# Mini_PLC_USB.net
KiCad netlist of a schematic drawn in EAGLE
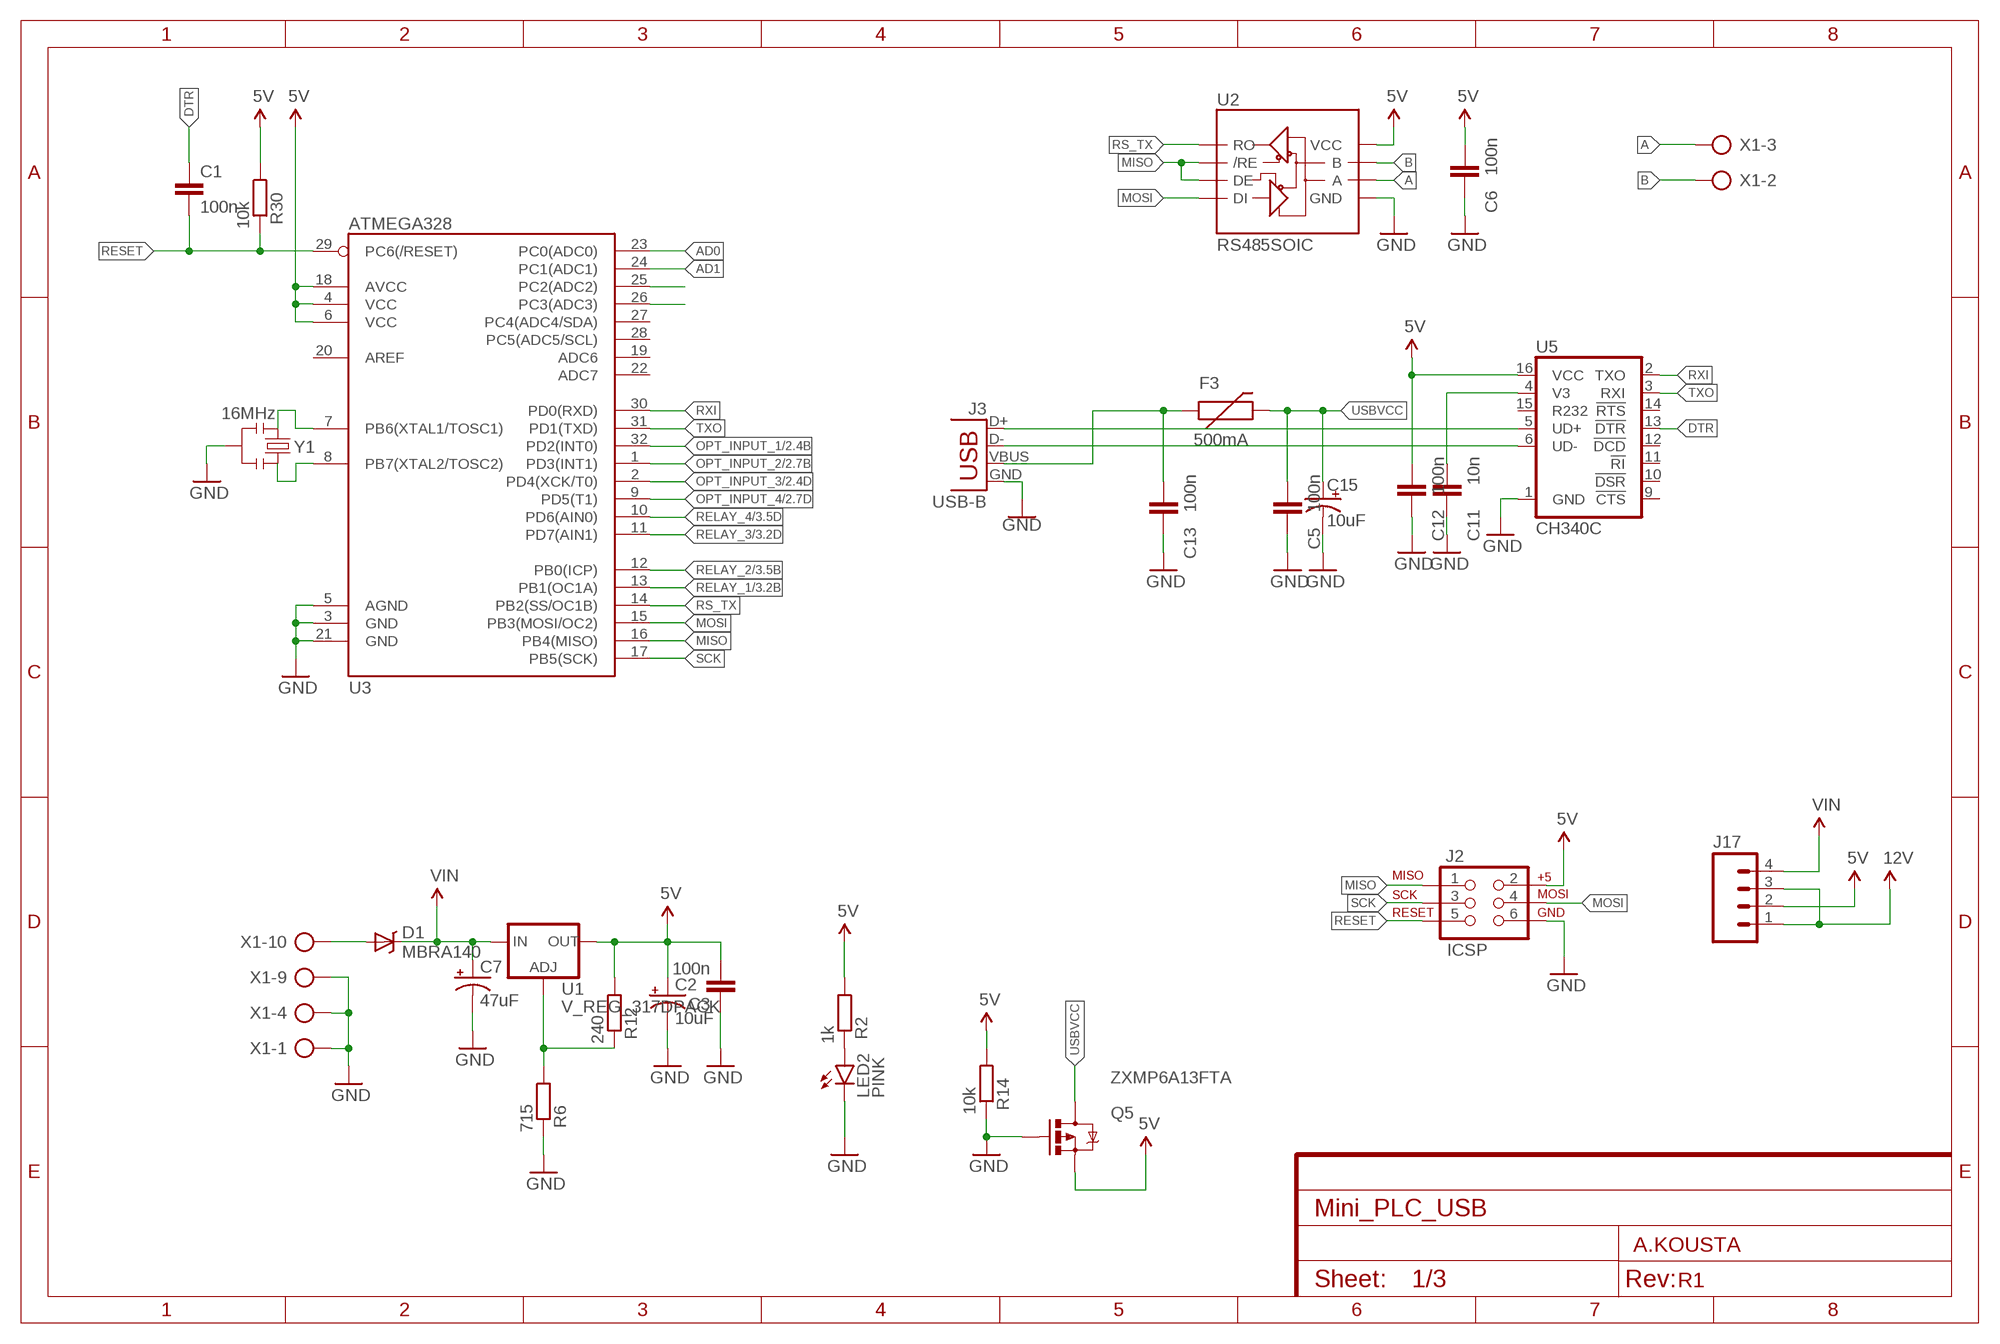
[diagram p0: schematic, sheet 1]
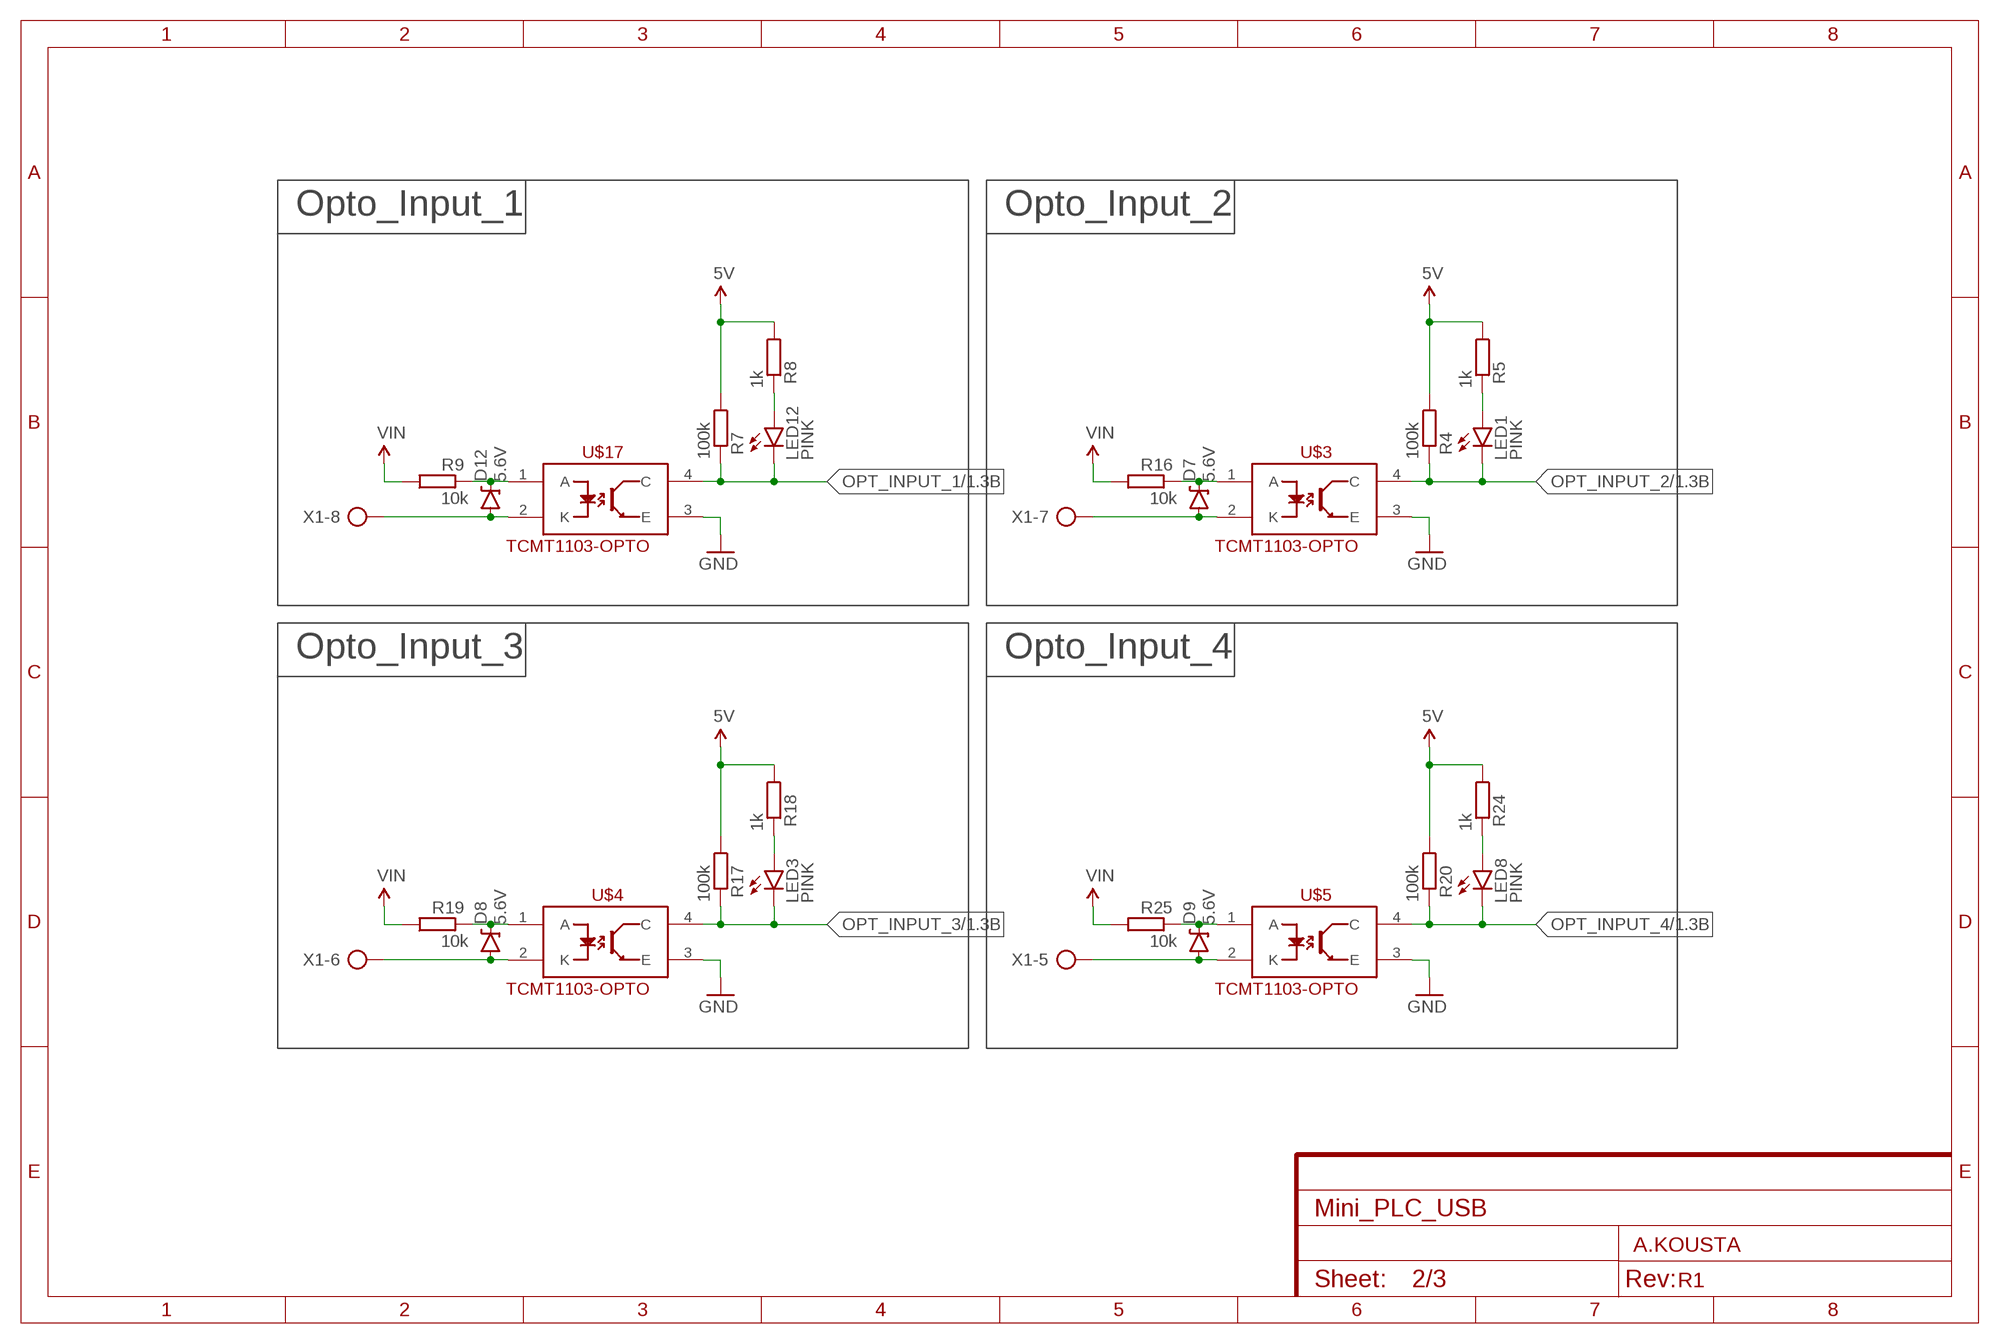
[diagram p1: schematic, sheet 2]
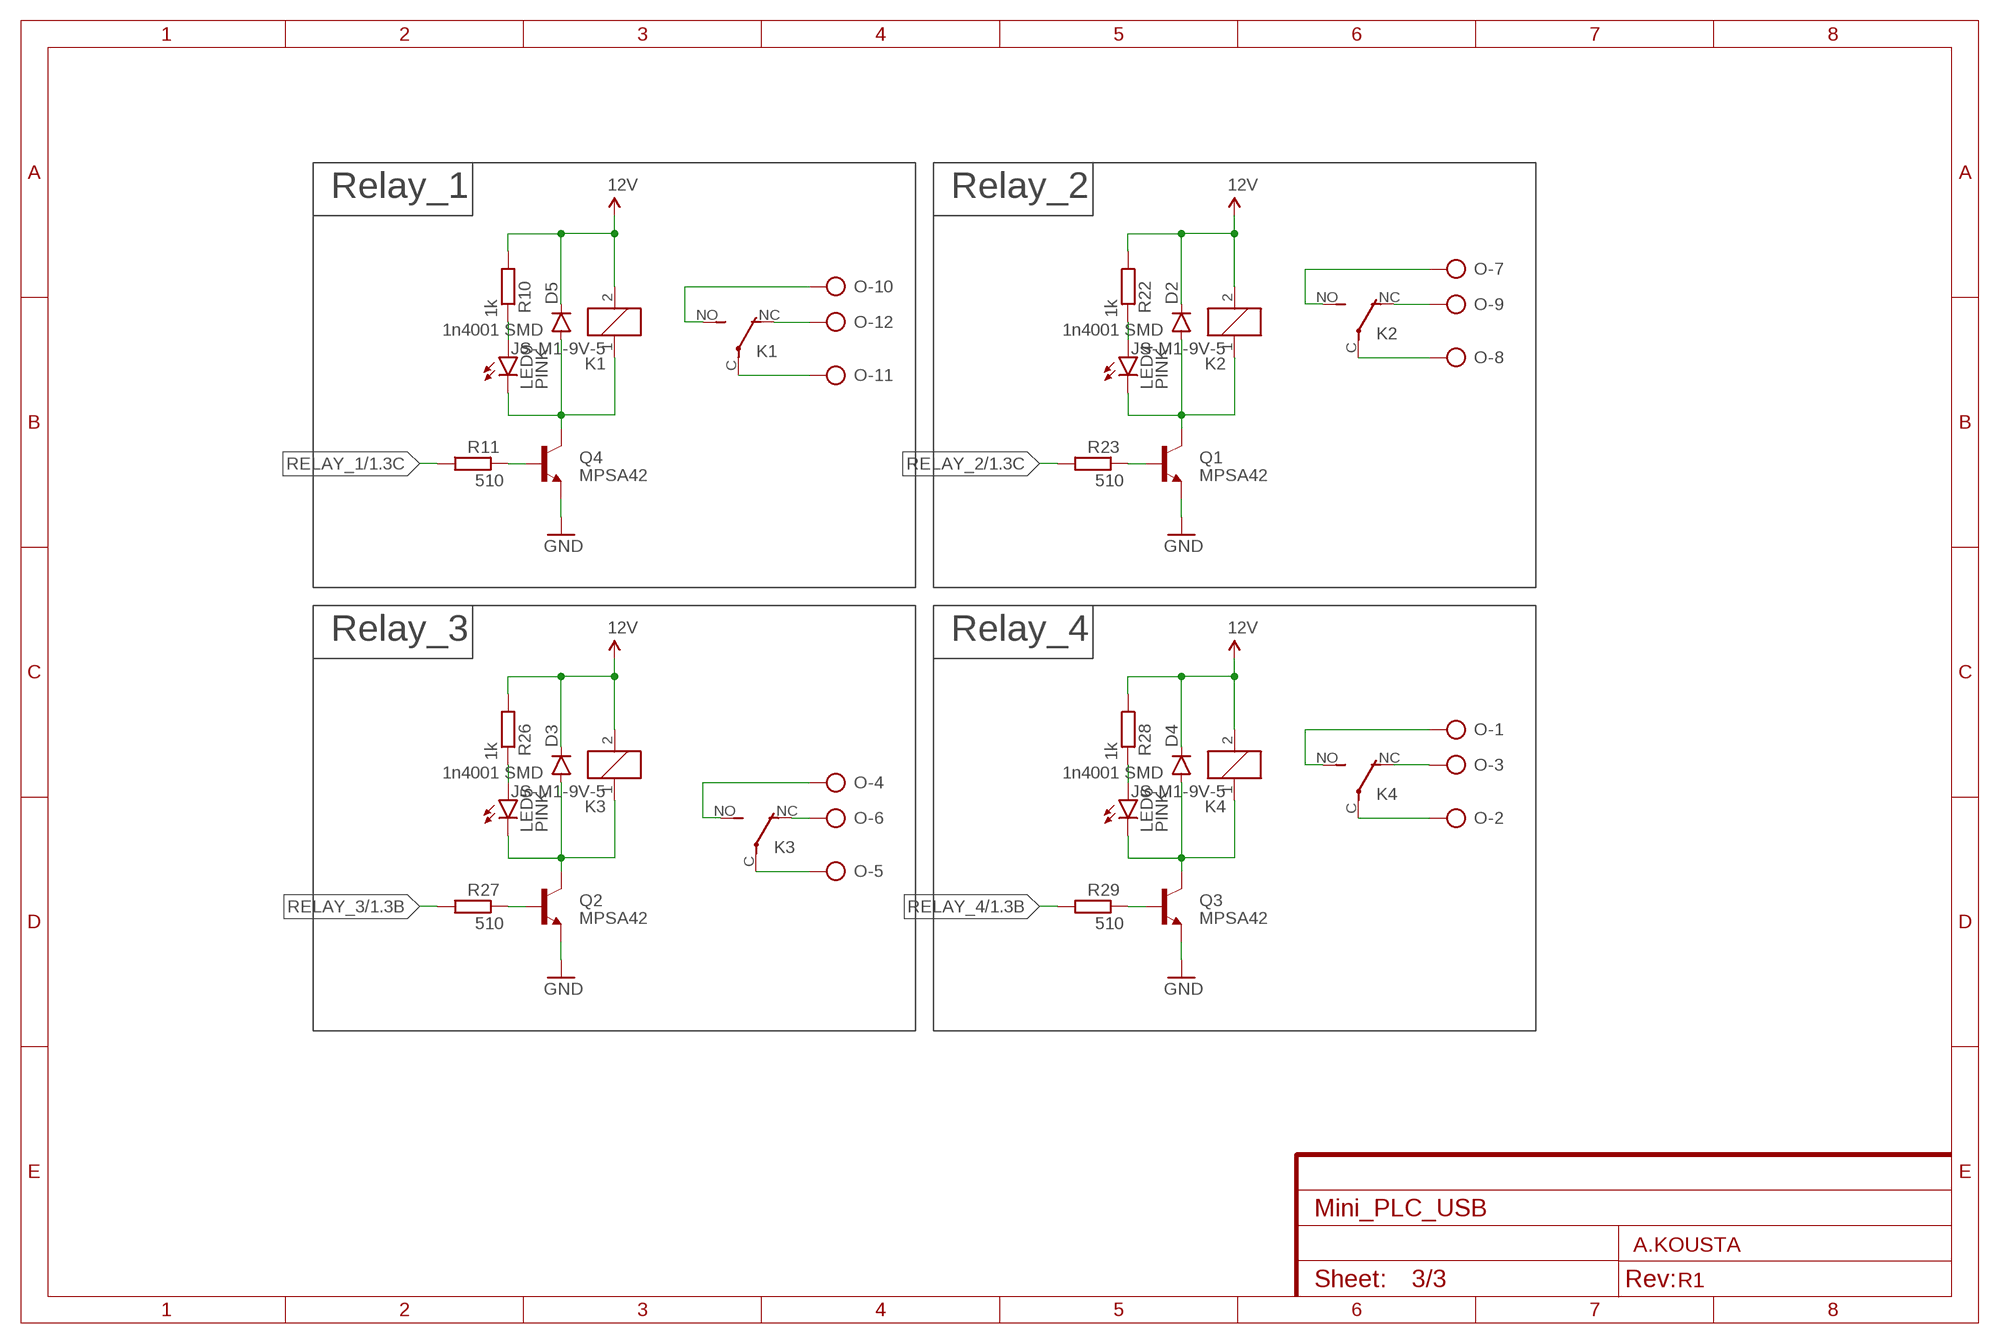
[diagram p2: schematic, sheet 3]

(export (version "E")
  (design (tool "Eeschema 10.0.6"))
  (components
    (comp (ref "D2")
      (value "1n4001 SMD")
      (footprint "eagle-import:SOD-123")
      (libsource (lib "eagle-import") (part "DIODESOD123"))
    )
    (comp (ref "D3")
      (value "1n4001 SMD")
      (footprint "eagle-import:SOD-123")
      (libsource (lib "eagle-import") (part "DIODESOD123"))
    )
    (comp (ref "D4")
      (value "1n4001 SMD")
      (footprint "eagle-import:SOD-123")
      (libsource (lib "eagle-import") (part "DIODESOD123"))
    )
    (comp (ref "D5")
      (value "1n4001 SMD")
      (footprint "eagle-import:SOD-123")
      (libsource (lib "eagle-import") (part "DIODESOD123"))
    )
    (comp (ref "K1")
      (value "JS-M1-9V-5")
      (footprint "eagle-import:JS-M")
      (libsource (lib "eagle-import") (part "JS-M1-9V-5"))
    )
    (comp (ref "K2")
      (value "JS-M1-9V-5")
      (footprint "eagle-import:JS-M")
      (libsource (lib "eagle-import") (part "JS-M1-9V-5"))
    )
    (comp (ref "K3")
      (value "JS-M1-9V-5")
      (footprint "eagle-import:JS-M")
      (libsource (lib "eagle-import") (part "JS-M1-9V-5"))
    )
    (comp (ref "K4")
      (value "JS-M1-9V-5")
      (footprint "eagle-import:JS-M")
      (libsource (lib "eagle-import") (part "JS-M1-9V-5"))
    )
    (comp (ref "LED4")
      (value "PINK")
      (footprint "eagle-import:LED-1206@1")
      (libsource (lib "eagle-import") (part "LED-PINK1206"))
    )
    (comp (ref "LED5")
      (value "PINK")
      (footprint "eagle-import:LED-1206@1")
      (libsource (lib "eagle-import") (part "LED-PINK1206"))
    )
    (comp (ref "LED6")
      (value "PINK")
      (footprint "eagle-import:LED-1206@1")
      (libsource (lib "eagle-import") (part "LED-PINK1206"))
    )
    (comp (ref "LED9")
      (value "PINK")
      (footprint "eagle-import:LED-1206@1")
      (libsource (lib "eagle-import") (part "LED-PINK1206"))
    )
    (comp (ref "O")
      (value "AK500/12-H")
      (footprint "eagle-import:AK500_12-H")
      (libsource (lib "eagle-import") (part "AK500/12-H"))
    )
    (comp (ref "Q1")
      (value "MPSA42")
      (footprint "eagle-import:SOT23-3@1")
      (libsource (lib "eagle-import") (part "TRANSISTOR_NPNMPSA42"))
    )
    (comp (ref "Q2")
      (value "MPSA42")
      (footprint "eagle-import:SOT23-3@1")
      (libsource (lib "eagle-import") (part "TRANSISTOR_NPNMPSA42"))
    )
    (comp (ref "Q3")
      (value "MPSA42")
      (footprint "eagle-import:SOT23-3@1")
      (libsource (lib "eagle-import") (part "TRANSISTOR_NPNMPSA42"))
    )
    (comp (ref "Q4")
      (value "MPSA42")
      (footprint "eagle-import:SOT23-3@1")
      (libsource (lib "eagle-import") (part "TRANSISTOR_NPNMPSA42"))
    )
    (comp (ref "R10")
      (value "1k")
      (footprint "eagle-import:M1206")
      (libsource (lib "eagle-import") (part "R-EU_M1206"))
    )
    (comp (ref "R11")
      (value "510")
      (footprint "eagle-import:M1206")
      (libsource (lib "eagle-import") (part "R-EU_M1206"))
    )
    (comp (ref "R22")
      (value "1k")
      (footprint "eagle-import:M1206")
      (libsource (lib "eagle-import") (part "R-EU_M1206"))
    )
    (comp (ref "R23")
      (value "510")
      (footprint "eagle-import:M1206")
      (libsource (lib "eagle-import") (part "R-EU_M1206"))
    )
    (comp (ref "R26")
      (value "1k")
      (footprint "eagle-import:M1206")
      (libsource (lib "eagle-import") (part "R-EU_M1206"))
    )
    (comp (ref "R27")
      (value "510")
      (footprint "eagle-import:M1206")
      (libsource (lib "eagle-import") (part "R-EU_M1206"))
    )
    (comp (ref "R28")
      (value "1k")
      (footprint "eagle-import:M1206")
      (libsource (lib "eagle-import") (part "R-EU_M1206"))
    )
    (comp (ref "R29")
      (value "510")
      (footprint "eagle-import:M1206")
      (libsource (lib "eagle-import") (part "R-EU_M1206"))
    )
    (comp (ref "D7")
      (value "5.6V")
      (footprint "eagle-import:SOD-323")
      (libsource (lib "eagle-import") (part "DIODE-ZENER5.6V"))
    )
    (comp (ref "D8")
      (value "5.6V")
      (footprint "eagle-import:SOD-323")
      (libsource (lib "eagle-import") (part "DIODE-ZENER5.6V"))
    )
    (comp (ref "D9")
      (value "5.6V")
      (footprint "eagle-import:SOD-323")
      (libsource (lib "eagle-import") (part "DIODE-ZENER5.6V"))
    )
    (comp (ref "D12")
      (value "5.6V")
      (footprint "eagle-import:SOD-323")
      (libsource (lib "eagle-import") (part "DIODE-ZENER5.6V"))
    )
    (comp (ref "LED1")
      (value "PINK")
      (footprint "eagle-import:LED-1206@1")
      (libsource (lib "eagle-import") (part "LED-PINK1206"))
    )
    (comp (ref "LED3")
      (value "PINK")
      (footprint "eagle-import:LED-1206@1")
      (libsource (lib "eagle-import") (part "LED-PINK1206"))
    )
    (comp (ref "LED8")
      (value "PINK")
      (footprint "eagle-import:LED-1206@1")
      (libsource (lib "eagle-import") (part "LED-PINK1206"))
    )
    (comp (ref "LED12")
      (value "PINK")
      (footprint "eagle-import:LED-1206@1")
      (libsource (lib "eagle-import") (part "LED-PINK1206"))
    )
    (comp (ref "R4")
      (value "100k")
      (footprint "eagle-import:M1206")
      (libsource (lib "eagle-import") (part "R-EU_M1206"))
    )
    (comp (ref "R5")
      (value "1k")
      (footprint "eagle-import:M1206")
      (libsource (lib "eagle-import") (part "R-EU_M1206"))
    )
    (comp (ref "R7")
      (value "100k")
      (footprint "eagle-import:M1206")
      (libsource (lib "eagle-import") (part "R-EU_M1206"))
    )
    (comp (ref "R8")
      (value "1k")
      (footprint "eagle-import:M1206")
      (libsource (lib "eagle-import") (part "R-EU_M1206"))
    )
    (comp (ref "R9")
      (value "10k")
      (footprint "eagle-import:M1206")
      (libsource (lib "eagle-import") (part "R-EU_M1206"))
    )
    (comp (ref "R16")
      (value "10k")
      (footprint "eagle-import:M1206")
      (libsource (lib "eagle-import") (part "R-EU_M1206"))
    )
    (comp (ref "R17")
      (value "100k")
      (footprint "eagle-import:M1206")
      (libsource (lib "eagle-import") (part "R-EU_M1206"))
    )
    (comp (ref "R18")
      (value "1k")
      (footprint "eagle-import:M1206")
      (libsource (lib "eagle-import") (part "R-EU_M1206"))
    )
    (comp (ref "R19")
      (value "10k")
      (footprint "eagle-import:M1206")
      (libsource (lib "eagle-import") (part "R-EU_M1206"))
    )
    (comp (ref "R20")
      (value "100k")
      (footprint "eagle-import:M1206")
      (libsource (lib "eagle-import") (part "R-EU_M1206"))
    )
    (comp (ref "R24")
      (value "1k")
      (footprint "eagle-import:M1206")
      (libsource (lib "eagle-import") (part "R-EU_M1206"))
    )
    (comp (ref "R25")
      (value "10k")
      (footprint "eagle-import:M1206")
      (libsource (lib "eagle-import") (part "R-EU_M1206"))
    )
    (comp (ref "U$3")
      (value "TCMT1103-OPTO")
      (footprint "eagle-import:SSOP-4")
      (libsource (lib "eagle-import") (part "TCMT1103-OPTO"))
    )
    (comp (ref "U$4")
      (value "TCMT1103-OPTO")
      (footprint "eagle-import:SSOP-4")
      (libsource (lib "eagle-import") (part "TCMT1103-OPTO"))
    )
    (comp (ref "U$5")
      (value "TCMT1103-OPTO")
      (footprint "eagle-import:SSOP-4")
      (libsource (lib "eagle-import") (part "TCMT1103-OPTO"))
    )
    (comp (ref "U$17")
      (value "TCMT1103-OPTO")
      (footprint "eagle-import:SSOP-4")
      (libsource (lib "eagle-import") (part "TCMT1103-OPTO"))
    )
    (comp (ref "X1")
      (value "AK500/10-H")
      (footprint "eagle-import:AK500_10-H")
      (libsource (lib "eagle-import") (part "AK500/10-H"))
    )
    (comp (ref "C1")
      (value "100n")
      (footprint "eagle-import:C1206")
      (libsource (lib "eagle-import") (part "C-EUC1206"))
    )
    (comp (ref "C2")
      (value "10uF")
      (footprint "eagle-import:EIA3216")
      (libsource (lib "eagle-import") (part "CAP_POL1206"))
    )
    (comp (ref "C3")
      (value "100n")
      (footprint "eagle-import:C1206")
      (libsource (lib "eagle-import") (part "C-EUC1206"))
    )
    (comp (ref "C5")
      (value "100n")
      (footprint "eagle-import:C1206")
      (libsource (lib "eagle-import") (part "C-EUC1206"))
    )
    (comp (ref "C6")
      (value "100n")
      (footprint "eagle-import:C1206")
      (libsource (lib "eagle-import") (part "C-EUC1206"))
    )
    (comp (ref "C7")
      (value "47uF")
      (footprint "eagle-import:PANASONIC_D")
      (fields (field (name "MF") "PANASONIC ELECTRONIC COMPONENTS") (field (name "MPN") "EEE1CA470SP"))
      (libsource (lib "eagle-import") (part "CAP_POLD"))
    )
    (comp (ref "C11")
      (value "10n")
      (footprint "eagle-import:C1206")
      (libsource (lib "eagle-import") (part "C-EUC1206"))
    )
    (comp (ref "C12")
      (value "100n")
      (footprint "eagle-import:C1206")
      (libsource (lib "eagle-import") (part "C-EUC1206"))
    )
    (comp (ref "C13")
      (value "100n")
      (footprint "eagle-import:C1206")
      (libsource (lib "eagle-import") (part "C-EUC1206"))
    )
    (comp (ref "C15")
      (value "10uF")
      (footprint "eagle-import:EIA3216")
      (libsource (lib "eagle-import") (part "10UF-POLAR-EIA3216-16V-10%(TANT)"))
    )
    (comp (ref "D1")
      (value "MBRA140")
      (footprint "eagle-import:SMA-DIODE")
      (fields (field (name "MF") "DIODES INC.") (field (name "MPN") "B140-13-F"))
      (libsource (lib "eagle-import") (part "DIODE-SCHOTTKY_"))
    )
    (comp (ref "F3")
      (value "500mA")
      (footprint "eagle-import:PTC-1206")
      (libsource (lib "eagle-import") (part "PTCSMD"))
    )
    (comp (ref "J2")
      (value "ICSP")
      (footprint "eagle-import:2X3")
      (libsource (lib "eagle-import") (part "AVR_SPI_PRG_6PTH"))
    )
    (comp (ref "J3")
      (value "USB-B")
      (footprint "eagle-import:USB-B-PTH")
      (fields (field (name "MPN") "USB-B-S-RA"))
      (libsource (lib "eagle-import") (part "USBPTH"))
    )
    (comp (ref "J17")
      (value "M04PTH")
      (footprint "eagle-import:1X04")
      (libsource (lib "eagle-import") (part "M04PTH"))
    )
    (comp (ref "LED2")
      (value "PINK")
      (footprint "eagle-import:LED-1206@1")
      (libsource (lib "eagle-import") (part "LED-PINK1206"))
    )
    (comp (ref "Q5")
      (value "ZXMP6A13FTA")
      (footprint "eagle-import:SOT23-3")
      (libsource (lib "eagle-import") (part "MOSFET-PCHANNELSMD"))
    )
    (comp (ref "R2")
      (value "1k")
      (footprint "eagle-import:M1206")
      (libsource (lib "eagle-import") (part "R-EU_M1206"))
    )
    (comp (ref "R6")
      (value "715")
      (footprint "eagle-import:M1206")
      (libsource (lib "eagle-import") (part "R-EU_M1206"))
    )
    (comp (ref "R12")
      (value "240")
      (footprint "eagle-import:M1206")
      (libsource (lib "eagle-import") (part "R-EU_M1206"))
    )
    (comp (ref "R14")
      (value "10k")
      (footprint "eagle-import:M1206")
      (libsource (lib "eagle-import") (part "R-EU_M1206"))
    )
    (comp (ref "R30")
      (value "10k")
      (footprint "eagle-import:M1206")
      (libsource (lib "eagle-import") (part "R-EU_M1206"))
    )
    (comp (ref "U1")
      (value "V_REG_317DPACK")
      (footprint "eagle-import:V-REG_DPACK")
      (libsource (lib "eagle-import") (part "V_REG_317DPACK"))
    )
    (comp (ref "U2")
      (value "RS485SOIC")
      (footprint "eagle-import:SO08")
      (libsource (lib "eagle-import") (part "RS485SOIC"))
    )
    (comp (ref "U3")
      (value "ATMEGA328")
      (footprint "eagle-import:TQFP32-08")
      (libsource (lib "eagle-import") (part "ATMEGA168"))
    )
    (comp (ref "U5")
      (value "CH340C")
      (footprint "eagle-import:SO016")
      (libsource (lib "eagle-import") (part "CH340C"))
    )
    (comp (ref "Y1")
      (value "16MHz")
      (footprint "eagle-import:RESONATOR-SMD")
      (libsource (lib "eagle-import") (part "RESONATORSMD"))
    )
  )
  (nets
    (net (code "1") (name "5V") (class "Default")
      (node (ref "C12") (pin "2") (pinfunction "2_2") (pintype "passive"))
      (node (ref "C2") (pin "A") (pinfunction "+_A") (pintype "passive"))
      (node (ref "C3") (pin "2") (pinfunction "2_2") (pintype "passive"))
      (node (ref "C6") (pin "2") (pinfunction "2_2") (pintype "passive"))
      (node (ref "J17") (pin "2") (pinfunction "2_2") (pintype "passive"))
      (node (ref "J2") (pin "2") (pinfunction "2_2") (pintype "passive"))
      (node (ref "Q5") (pin "2") (pinfunction "S_2") (pintype "passive"))
      (node (ref "R12") (pin "1") (pinfunction "1_1") (pintype "passive"))
      (node (ref "R14") (pin "1") (pinfunction "1_1") (pintype "passive"))
      (node (ref "R17") (pin "1") (pinfunction "1_1") (pintype "passive"))
      (node (ref "R18") (pin "1") (pinfunction "1_1") (pintype "passive"))
      (node (ref "R2") (pin "1") (pinfunction "1_1") (pintype "passive"))
      (node (ref "R20") (pin "1") (pinfunction "1_1") (pintype "passive"))
      (node (ref "R24") (pin "1") (pinfunction "1_1") (pintype "passive"))
      (node (ref "R30") (pin "1") (pinfunction "1_1") (pintype "passive"))
      (node (ref "R4") (pin "1") (pinfunction "1_1") (pintype "passive"))
      (node (ref "R5") (pin "1") (pinfunction "1_1") (pintype "passive"))
      (node (ref "R7") (pin "1") (pinfunction "1_1") (pintype "passive"))
      (node (ref "R8") (pin "1") (pinfunction "1_1") (pintype "passive"))
      (node (ref "U1") (pin "4") (pinfunction "OUT_4") (pintype "output"))
      (node (ref "U2") (pin "8") (pinfunction "VCC_8") (pintype "bidirectional"))
      (node (ref "U3") (pin "18") (pinfunction "AVCC_18") (pintype "bidirectional"))
      (node (ref "U3") (pin "4") (pinfunction "VCC_4") (pintype "bidirectional"))
      (node (ref "U3") (pin "6") (pinfunction "VCC_6") (pintype "bidirectional"))
      (node (ref "U5") (pin "16") (pinfunction "VCC_16") (pintype "bidirectional"))
    )
    (net (code "2") (name "12V") (class "Default")
      (node (ref "D2") (pin "C") (pinfunction "C_C") (pintype "passive"))
      (node (ref "D3") (pin "C") (pinfunction "C_C") (pintype "passive"))
      (node (ref "D4") (pin "C") (pinfunction "C_C") (pintype "passive"))
      (node (ref "D5") (pin "C") (pinfunction "C_C") (pintype "passive"))
      (node (ref "J17") (pin "1") (pinfunction "1_1") (pintype "passive"))
      (node (ref "J17") (pin "3") (pinfunction "3_3") (pintype "passive"))
      (node (ref "K1") (pin "2") (pinfunction "2_2") (pintype "passive"))
      (node (ref "K2") (pin "2") (pinfunction "2_2") (pintype "passive"))
      (node (ref "K3") (pin "2") (pinfunction "2_2") (pintype "passive"))
      (node (ref "K4") (pin "2") (pinfunction "2_2") (pintype "passive"))
      (node (ref "R10") (pin "1") (pinfunction "1_1") (pintype "passive"))
      (node (ref "R22") (pin "1") (pinfunction "1_1") (pintype "passive"))
      (node (ref "R26") (pin "1") (pinfunction "1_1") (pintype "passive"))
      (node (ref "R28") (pin "1") (pinfunction "1_1") (pintype "passive"))
    )
    (net (code "3") (name "A") (class "Default")
      (node (ref "U2") (pin "6") (pinfunction "A_6") (pintype "bidirectional"))
      (node (ref "X1") (pin "3") (pinfunction "KL_3") (pintype "passive"))
    )
    (net (code "4") (name "AD0") (class "Default")
      (node (ref "U3") (pin "23") (pinfunction "PC0(ADC0)_23") (pintype "bidirectional"))
    )
    (net (code "5") (name "AD1") (class "Default")
      (node (ref "U3") (pin "24") (pinfunction "PC1(ADC1)_24") (pintype "bidirectional"))
    )
    (net (code "6") (name "B") (class "Default")
      (node (ref "U2") (pin "7") (pinfunction "B_7") (pintype "bidirectional"))
      (node (ref "X1") (pin "2") (pinfunction "KL_2") (pintype "passive"))
    )
    (net (code "7") (name "DTR") (class "Default")
      (node (ref "C1") (pin "1") (pinfunction "1_1") (pintype "passive"))
      (node (ref "U5") (pin "13") (pinfunction "~{DTR}_13") (pintype "bidirectional"))
    )
    (net (code "8") (name "GND") (class "Default")
      (node (ref "C11") (pin "1") (pinfunction "1_1") (pintype "passive"))
      (node (ref "C12") (pin "1") (pinfunction "1_1") (pintype "passive"))
      (node (ref "C13") (pin "1") (pinfunction "1_1") (pintype "passive"))
      (node (ref "C15") (pin "-") (pinfunction "-_-") (pintype "passive"))
      (node (ref "C2") (pin "C") (pinfunction "-_C") (pintype "passive"))
      (node (ref "C3") (pin "1") (pinfunction "1_1") (pintype "passive"))
      (node (ref "C5") (pin "1") (pinfunction "1_1") (pintype "passive"))
      (node (ref "C6") (pin "1") (pinfunction "1_1") (pintype "passive"))
      (node (ref "C7") (pin "-") (pinfunction "-_-") (pintype "passive"))
      (node (ref "J2") (pin "6") (pinfunction "6_6") (pintype "passive"))
      (node (ref "J3") (pin "GND") (pinfunction "GND_GND") (pintype "bidirectional"))
      (node (ref "LED2") (pin "C") (pinfunction "C_C") (pintype "passive"))
      (node (ref "Q1") (pin "2") (pinfunction "E_2") (pintype "passive"))
      (node (ref "Q2") (pin "2") (pinfunction "E_2") (pintype "passive"))
      (node (ref "Q3") (pin "2") (pinfunction "E_2") (pintype "passive"))
      (node (ref "Q4") (pin "2") (pinfunction "E_2") (pintype "passive"))
      (node (ref "Q5") (pin "1") (pinfunction "G_1") (pintype "passive"))
      (node (ref "R14") (pin "2") (pinfunction "2_2") (pintype "passive"))
      (node (ref "R6") (pin "2") (pinfunction "2_2") (pintype "passive"))
      (node (ref "U$17") (pin "3") (pinfunction "E_3") (pintype "bidirectional"))
      (node (ref "U$3") (pin "3") (pinfunction "E_3") (pintype "bidirectional"))
      (node (ref "U$4") (pin "3") (pinfunction "E_3") (pintype "bidirectional"))
      (node (ref "U$5") (pin "3") (pinfunction "E_3") (pintype "bidirectional"))
      (node (ref "U2") (pin "5") (pinfunction "GND_5") (pintype "bidirectional"))
      (node (ref "U3") (pin "21") (pinfunction "GND_21") (pintype "bidirectional"))
      (node (ref "U3") (pin "3") (pinfunction "GND_3") (pintype "bidirectional"))
      (node (ref "U3") (pin "5") (pinfunction "AGND_5") (pintype "bidirectional"))
      (node (ref "U5") (pin "1") (pinfunction "GND_1") (pintype "bidirectional"))
      (node (ref "X1") (pin "1") (pinfunction "KL_1") (pintype "passive"))
      (node (ref "X1") (pin "4") (pinfunction "KL_4") (pintype "passive"))
      (node (ref "X1") (pin "9") (pinfunction "KL_9") (pintype "passive"))
      (node (ref "Y1") (pin "2") (pinfunction "2_2") (pintype "passive"))
    )
    (net (code "9") (name "MISO") (class "Default")
      (node (ref "J2") (pin "1") (pinfunction "1_1") (pintype "passive"))
      (node (ref "U2") (pin "2") (pinfunction "/RE_2") (pintype "bidirectional"))
      (node (ref "U2") (pin "3") (pinfunction "DE_3") (pintype "bidirectional"))
      (node (ref "U3") (pin "16") (pinfunction "PB4(MISO)_16") (pintype "bidirectional"))
    )
    (net (code "10") (name "MOSI") (class "Default")
      (node (ref "J2") (pin "4") (pinfunction "4_4") (pintype "passive"))
      (node (ref "U2") (pin "4") (pinfunction "DI_4") (pintype "bidirectional"))
      (node (ref "U3") (pin "15") (pinfunction "PB3(MOSI/OC2)_15") (pintype "bidirectional"))
    )
    (net (code "11") (name "Net-(C13-Pad2)") (class "Default")
      (node (ref "C13") (pin "2") (pinfunction "2_2") (pintype "passive"))
      (node (ref "F3") (pin "1") (pinfunction "1_1") (pintype "bidirectional"))
      (node (ref "J3") (pin "VBUS") (pinfunction "VBUS_VBUS") (pintype "bidirectional"))
    )
    (net (code "12") (name "Net-(K1B-O)") (class "Default")
      (node (ref "K1") (pin "NC") (pinfunction "O_NC") (pintype "passive"))
      (node (ref "O") (pin "12") (pinfunction "KL_12") (pintype "passive"))
    )
    (net (code "13") (name "Net-(K1B-P)") (class "Default")
      (node (ref "K1") (pin "C") (pinfunction "P_C") (pintype "passive"))
      (node (ref "O") (pin "11") (pinfunction "KL_11") (pintype "passive"))
    )
    (net (code "14") (name "Net-(K1B-S)") (class "Default")
      (node (ref "K1") (pin "NO") (pinfunction "S_NO") (pintype "passive"))
      (node (ref "O") (pin "10") (pinfunction "KL_10") (pintype "passive"))
    )
    (net (code "15") (name "Net-(K2B-O)") (class "Default")
      (node (ref "K2") (pin "NC") (pinfunction "O_NC") (pintype "passive"))
      (node (ref "O") (pin "9") (pinfunction "KL_9") (pintype "passive"))
    )
    (net (code "16") (name "Net-(K2B-P)") (class "Default")
      (node (ref "K2") (pin "C") (pinfunction "P_C") (pintype "passive"))
      (node (ref "O") (pin "8") (pinfunction "KL_8") (pintype "passive"))
    )
    (net (code "17") (name "Net-(K2B-S)") (class "Default")
      (node (ref "K2") (pin "NO") (pinfunction "S_NO") (pintype "passive"))
      (node (ref "O") (pin "7") (pinfunction "KL_7") (pintype "passive"))
    )
    (net (code "18") (name "Net-(K3B-O)") (class "Default")
      (node (ref "K3") (pin "NC") (pinfunction "O_NC") (pintype "passive"))
      (node (ref "O") (pin "6") (pinfunction "KL_6") (pintype "passive"))
    )
    (net (code "19") (name "Net-(K3B-P)") (class "Default")
      (node (ref "K3") (pin "C") (pinfunction "P_C") (pintype "passive"))
      (node (ref "O") (pin "5") (pinfunction "KL_5") (pintype "passive"))
    )
    (net (code "20") (name "Net-(K3B-S)") (class "Default")
      (node (ref "K3") (pin "NO") (pinfunction "S_NO") (pintype "passive"))
      (node (ref "O") (pin "4") (pinfunction "KL_4") (pintype "passive"))
    )
    (net (code "21") (name "Net-(K4B-O)") (class "Default")
      (node (ref "K4") (pin "NC") (pinfunction "O_NC") (pintype "passive"))
      (node (ref "O") (pin "3") (pinfunction "KL_3") (pintype "passive"))
    )
    (net (code "22") (name "Net-(K4B-P)") (class "Default")
      (node (ref "K4") (pin "C") (pinfunction "P_C") (pintype "passive"))
      (node (ref "O") (pin "2") (pinfunction "KL_2") (pintype "passive"))
    )
    (net (code "23") (name "Net-(K4B-S)") (class "Default")
      (node (ref "K4") (pin "NO") (pinfunction "S_NO") (pintype "passive"))
      (node (ref "O") (pin "1") (pinfunction "KL_1") (pintype "passive"))
    )
    (net (code "24") (name "Net-(LED1-PadA)") (class "Default")
      (node (ref "LED1") (pin "A") (pinfunction "A_A") (pintype "passive"))
      (node (ref "R5") (pin "2") (pinfunction "2_2") (pintype "passive"))
    )
    (net (code "25") (name "Net-(LED2-PadA)") (class "Default")
      (node (ref "LED2") (pin "A") (pinfunction "A_A") (pintype "passive"))
      (node (ref "R2") (pin "2") (pinfunction "2_2") (pintype "passive"))
    )
    (net (code "26") (name "Net-(LED3-PadA)") (class "Default")
      (node (ref "LED3") (pin "A") (pinfunction "A_A") (pintype "passive"))
      (node (ref "R18") (pin "2") (pinfunction "2_2") (pintype "passive"))
    )
    (net (code "27") (name "Net-(LED4-PadA)") (class "Default")
      (node (ref "LED4") (pin "A") (pinfunction "A_A") (pintype "passive"))
      (node (ref "R22") (pin "2") (pinfunction "2_2") (pintype "passive"))
    )
    (net (code "28") (name "Net-(LED5-PadA)") (class "Default")
      (node (ref "LED5") (pin "A") (pinfunction "A_A") (pintype "passive"))
      (node (ref "R26") (pin "2") (pinfunction "2_2") (pintype "passive"))
    )
    (net (code "29") (name "Net-(LED6-PadA)") (class "Default")
      (node (ref "LED6") (pin "A") (pinfunction "A_A") (pintype "passive"))
      (node (ref "R28") (pin "2") (pinfunction "2_2") (pintype "passive"))
    )
    (net (code "30") (name "Net-(LED8-PadA)") (class "Default")
      (node (ref "LED8") (pin "A") (pinfunction "A_A") (pintype "passive"))
      (node (ref "R24") (pin "2") (pinfunction "2_2") (pintype "passive"))
    )
    (net (code "31") (name "Net-(LED9-PadA)") (class "Default")
      (node (ref "LED9") (pin "A") (pinfunction "A_A") (pintype "passive"))
      (node (ref "R10") (pin "2") (pinfunction "2_2") (pintype "passive"))
    )
    (net (code "32") (name "Net-(LED12-PadA)") (class "Default")
      (node (ref "LED12") (pin "A") (pinfunction "A_A") (pintype "passive"))
      (node (ref "R8") (pin "2") (pinfunction "2_2") (pintype "passive"))
    )
    (net (code "33") (name "Net-(Q1-B)") (class "Default")
      (node (ref "Q1") (pin "1") (pinfunction "B_1") (pintype "passive"))
      (node (ref "R23") (pin "2") (pinfunction "2_2") (pintype "passive"))
    )
    (net (code "34") (name "Net-(Q1-C)") (class "Default")
      (node (ref "D2") (pin "A") (pinfunction "A_A") (pintype "passive"))
      (node (ref "K2") (pin "1") (pinfunction "1_1") (pintype "passive"))
      (node (ref "LED4") (pin "C") (pinfunction "C_C") (pintype "passive"))
      (node (ref "Q1") (pin "3") (pinfunction "C_3") (pintype "passive"))
    )
    (net (code "35") (name "Net-(Q2-B)") (class "Default")
      (node (ref "Q2") (pin "1") (pinfunction "B_1") (pintype "passive"))
      (node (ref "R27") (pin "2") (pinfunction "2_2") (pintype "passive"))
    )
    (net (code "36") (name "Net-(Q2-C)") (class "Default")
      (node (ref "D3") (pin "A") (pinfunction "A_A") (pintype "passive"))
      (node (ref "K3") (pin "1") (pinfunction "1_1") (pintype "passive"))
      (node (ref "LED5") (pin "C") (pinfunction "C_C") (pintype "passive"))
      (node (ref "Q2") (pin "3") (pinfunction "C_3") (pintype "passive"))
    )
    (net (code "37") (name "Net-(Q3-B)") (class "Default")
      (node (ref "Q3") (pin "1") (pinfunction "B_1") (pintype "passive"))
      (node (ref "R29") (pin "2") (pinfunction "2_2") (pintype "passive"))
    )
    (net (code "38") (name "Net-(Q3-C)") (class "Default")
      (node (ref "D4") (pin "A") (pinfunction "A_A") (pintype "passive"))
      (node (ref "K4") (pin "1") (pinfunction "1_1") (pintype "passive"))
      (node (ref "LED6") (pin "C") (pinfunction "C_C") (pintype "passive"))
      (node (ref "Q3") (pin "3") (pinfunction "C_3") (pintype "passive"))
    )
    (net (code "39") (name "Net-(Q4-B)") (class "Default")
      (node (ref "Q4") (pin "1") (pinfunction "B_1") (pintype "passive"))
      (node (ref "R11") (pin "2") (pinfunction "2_2") (pintype "passive"))
    )
    (net (code "40") (name "Net-(Q4-C)") (class "Default")
      (node (ref "D5") (pin "A") (pinfunction "A_A") (pintype "passive"))
      (node (ref "K1") (pin "1") (pinfunction "1_1") (pintype "passive"))
      (node (ref "LED9") (pin "C") (pinfunction "C_C") (pintype "passive"))
      (node (ref "Q4") (pin "3") (pinfunction "C_3") (pintype "passive"))
    )
    (net (code "41") (name "Net-(U$3-A)") (class "Default")
      (node (ref "D7") (pin "C") (pinfunction "C_C") (pintype "passive"))
      (node (ref "R16") (pin "2") (pinfunction "2_2") (pintype "passive"))
      (node (ref "U$3") (pin "1") (pinfunction "A_1") (pintype "bidirectional"))
    )
    (net (code "42") (name "Net-(U$3-K)") (class "Default")
      (node (ref "D7") (pin "A") (pinfunction "A_A") (pintype "passive"))
      (node (ref "U$3") (pin "2") (pinfunction "K_2") (pintype "bidirectional"))
      (node (ref "X1") (pin "7") (pinfunction "KL_7") (pintype "passive"))
    )
    (net (code "43") (name "Net-(U$4-A)") (class "Default")
      (node (ref "D8") (pin "C") (pinfunction "C_C") (pintype "passive"))
      (node (ref "R19") (pin "2") (pinfunction "2_2") (pintype "passive"))
      (node (ref "U$4") (pin "1") (pinfunction "A_1") (pintype "bidirectional"))
    )
    (net (code "44") (name "Net-(U$4-K)") (class "Default")
      (node (ref "D8") (pin "A") (pinfunction "A_A") (pintype "passive"))
      (node (ref "U$4") (pin "2") (pinfunction "K_2") (pintype "bidirectional"))
      (node (ref "X1") (pin "6") (pinfunction "KL_6") (pintype "passive"))
    )
    (net (code "45") (name "Net-(U$5-A)") (class "Default")
      (node (ref "D9") (pin "C") (pinfunction "C_C") (pintype "passive"))
      (node (ref "R25") (pin "2") (pinfunction "2_2") (pintype "passive"))
      (node (ref "U$5") (pin "1") (pinfunction "A_1") (pintype "bidirectional"))
    )
    (net (code "46") (name "Net-(U$5-K)") (class "Default")
      (node (ref "D9") (pin "A") (pinfunction "A_A") (pintype "passive"))
      (node (ref "U$5") (pin "2") (pinfunction "K_2") (pintype "bidirectional"))
      (node (ref "X1") (pin "5") (pinfunction "KL_5") (pintype "passive"))
    )
    (net (code "47") (name "Net-(U$17-A)") (class "Default")
      (node (ref "D12") (pin "C") (pinfunction "C_C") (pintype "passive"))
      (node (ref "R9") (pin "2") (pinfunction "2_2") (pintype "passive"))
      (node (ref "U$17") (pin "1") (pinfunction "A_1") (pintype "bidirectional"))
    )
    (net (code "48") (name "Net-(U$17-K)") (class "Default")
      (node (ref "D12") (pin "A") (pinfunction "A_A") (pintype "passive"))
      (node (ref "U$17") (pin "2") (pinfunction "K_2") (pintype "bidirectional"))
      (node (ref "X1") (pin "8") (pinfunction "KL_8") (pintype "passive"))
    )
    (net (code "49") (name "Net-(U1-ADJ)") (class "Default")
      (node (ref "R12") (pin "2") (pinfunction "2_2") (pintype "passive"))
      (node (ref "R6") (pin "1") (pinfunction "1_1") (pintype "passive"))
      (node (ref "U1") (pin "1") (pinfunction "ADJ_1") (pintype "input"))
    )
    (net (code "50") (name "Net-(U3-PB6(XTAL1{slash}TOSC1))") (class "Default")
      (node (ref "U3") (pin "7") (pinfunction "PB6(XTAL1/TOSC1)_7") (pintype "bidirectional"))
      (node (ref "Y1") (pin "1") (pinfunction "1_1") (pintype "passive"))
    )
    (net (code "51") (name "Net-(U3-PB7(XTAL2{slash}TOSC2))") (class "Default")
      (node (ref "U3") (pin "8") (pinfunction "PB7(XTAL2/TOSC2)_8") (pintype "bidirectional"))
      (node (ref "Y1") (pin "3") (pinfunction "3_3") (pintype "passive"))
    )
    (net (code "52") (name "Net-(U5-UD+)") (class "Default")
      (node (ref "J3") (pin "D+") (pinfunction "D+_D+") (pintype "bidirectional"))
      (node (ref "U5") (pin "5") (pinfunction "UD+_5") (pintype "bidirectional"))
    )
    (net (code "53") (name "Net-(U5-UD-)") (class "Default")
      (node (ref "J3") (pin "D-") (pinfunction "D-_D-") (pintype "bidirectional"))
      (node (ref "U5") (pin "6") (pinfunction "UD-_6") (pintype "bidirectional"))
    )
    (net (code "54") (name "Net-(U5-V3)") (class "Default")
      (node (ref "C11") (pin "2") (pinfunction "2_2") (pintype "passive"))
      (node (ref "U5") (pin "4") (pinfunction "V3_4") (pintype "bidirectional"))
    )
    (net (code "55") (name "Net-(X1B-KL)") (class "Default")
      (node (ref "D1") (pin "A") (pinfunction "A_A") (pintype "passive"))
      (node (ref "X1") (pin "10") (pinfunction "KL_10") (pintype "passive"))
    )
    (net (code "56") (name "OPT_INPUT_1") (class "Default")
      (node (ref "LED12") (pin "C") (pinfunction "C_C") (pintype "passive"))
      (node (ref "R7") (pin "2") (pinfunction "2_2") (pintype "passive"))
      (node (ref "U$17") (pin "4") (pinfunction "C_4") (pintype "bidirectional"))
      (node (ref "U3") (pin "32") (pinfunction "PD2(INT0)_32") (pintype "bidirectional"))
    )
    (net (code "57") (name "OPT_INPUT_2") (class "Default")
      (node (ref "LED1") (pin "C") (pinfunction "C_C") (pintype "passive"))
      (node (ref "R4") (pin "2") (pinfunction "2_2") (pintype "passive"))
      (node (ref "U$3") (pin "4") (pinfunction "C_4") (pintype "bidirectional"))
      (node (ref "U3") (pin "1") (pinfunction "PD3(INT1)_1") (pintype "bidirectional"))
    )
    (net (code "58") (name "OPT_INPUT_3") (class "Default")
      (node (ref "LED3") (pin "C") (pinfunction "C_C") (pintype "passive"))
      (node (ref "R17") (pin "2") (pinfunction "2_2") (pintype "passive"))
      (node (ref "U$4") (pin "4") (pinfunction "C_4") (pintype "bidirectional"))
      (node (ref "U3") (pin "2") (pinfunction "PD4(XCK/T0)_2") (pintype "bidirectional"))
    )
    (net (code "59") (name "OPT_INPUT_4") (class "Default")
      (node (ref "LED8") (pin "C") (pinfunction "C_C") (pintype "passive"))
      (node (ref "R20") (pin "2") (pinfunction "2_2") (pintype "passive"))
      (node (ref "U$5") (pin "4") (pinfunction "C_4") (pintype "bidirectional"))
      (node (ref "U3") (pin "9") (pinfunction "PD5(T1)_9") (pintype "bidirectional"))
    )
    (net (code "60") (name "RELAY_1") (class "Default")
      (node (ref "R11") (pin "1") (pinfunction "1_1") (pintype "passive"))
      (node (ref "U3") (pin "13") (pinfunction "PB1(OC1A)_13") (pintype "bidirectional"))
    )
    (net (code "61") (name "RELAY_2") (class "Default")
      (node (ref "R23") (pin "1") (pinfunction "1_1") (pintype "passive"))
      (node (ref "U3") (pin "12") (pinfunction "PB0(ICP)_12") (pintype "bidirectional"))
    )
    (net (code "62") (name "RELAY_3") (class "Default")
      (node (ref "R27") (pin "1") (pinfunction "1_1") (pintype "passive"))
      (node (ref "U3") (pin "11") (pinfunction "PD7(AIN1)_11") (pintype "bidirectional"))
    )
    (net (code "63") (name "RELAY_4") (class "Default")
      (node (ref "R29") (pin "1") (pinfunction "1_1") (pintype "passive"))
      (node (ref "U3") (pin "10") (pinfunction "PD6(AIN0)_10") (pintype "bidirectional"))
    )
    (net (code "64") (name "RESET") (class "Default")
      (node (ref "C1") (pin "2") (pinfunction "2_2") (pintype "passive"))
      (node (ref "J2") (pin "5") (pinfunction "5_5") (pintype "passive"))
      (node (ref "R30") (pin "2") (pinfunction "2_2") (pintype "passive"))
      (node (ref "U3") (pin "29") (pinfunction "PC6(/RESET)_29") (pintype "bidirectional"))
    )
    (net (code "65") (name "RS_TX") (class "Default")
      (node (ref "U2") (pin "1") (pinfunction "RO_1") (pintype "bidirectional"))
      (node (ref "U3") (pin "14") (pinfunction "PB2(SS/OC1B)_14") (pintype "bidirectional"))
    )
    (net (code "66") (name "RXI") (class "Default")
      (node (ref "U3") (pin "30") (pinfunction "PD0(RXD)_30") (pintype "bidirectional"))
      (node (ref "U5") (pin "2") (pinfunction "TXO_2") (pintype "bidirectional"))
    )
    (net (code "67") (name "SCK") (class "Default")
      (node (ref "J2") (pin "3") (pinfunction "3_3") (pintype "passive"))
      (node (ref "U3") (pin "17") (pinfunction "PB5(SCK)_17") (pintype "bidirectional"))
    )
    (net (code "68") (name "TXO") (class "Default")
      (node (ref "U3") (pin "31") (pinfunction "PD1(TXD)_31") (pintype "bidirectional"))
      (node (ref "U5") (pin "3") (pinfunction "RXI_3") (pintype "bidirectional"))
    )
    (net (code "69") (name "USBVCC") (class "Default")
      (node (ref "C15") (pin "+") (pinfunction "+_+") (pintype "passive"))
      (node (ref "C5") (pin "2") (pinfunction "2_2") (pintype "passive"))
      (node (ref "F3") (pin "2") (pinfunction "2_2") (pintype "bidirectional"))
      (node (ref "Q5") (pin "3") (pinfunction "D_3") (pintype "passive"))
    )
    (net (code "70") (name "VIN") (class "Default")
      (node (ref "C7") (pin "+") (pinfunction "+_+") (pintype "passive"))
      (node (ref "D1") (pin "C") (pinfunction "C_C") (pintype "passive"))
      (node (ref "J17") (pin "4") (pinfunction "4_4") (pintype "passive"))
      (node (ref "R16") (pin "1") (pinfunction "1_1") (pintype "passive"))
      (node (ref "R19") (pin "1") (pinfunction "1_1") (pintype "passive"))
      (node (ref "R25") (pin "1") (pinfunction "1_1") (pintype "passive"))
      (node (ref "R9") (pin "1") (pinfunction "1_1") (pintype "passive"))
      (node (ref "U1") (pin "3") (pinfunction "IN_3") (pintype "input"))
    )
    (net (code "71") (name "unconnected-(U3-ADC6-Pad19)") (class "Default")
      (node (ref "U3") (pin "19") (pinfunction "ADC6_19") (pintype "bidirectional"))
    )
    (net (code "72") (name "unconnected-(U3-ADC7-Pad22)") (class "Default")
      (node (ref "U3") (pin "22") (pinfunction "ADC7_22") (pintype "bidirectional"))
    )
    (net (code "73") (name "unconnected-(U3-AREF-Pad20)") (class "Default")
      (node (ref "U3") (pin "20") (pinfunction "AREF_20") (pintype "bidirectional"))
    )
    (net (code "74") (name "unconnected-(U3-PC2(ADC2)-Pad25)") (class "Default")
      (node (ref "U3") (pin "25") (pinfunction "PC2(ADC2)_25") (pintype "bidirectional"))
    )
    (net (code "75") (name "unconnected-(U3-PC3(ADC3)-Pad26)") (class "Default")
      (node (ref "U3") (pin "26") (pinfunction "PC3(ADC3)_26") (pintype "bidirectional"))
    )
    (net (code "76") (name "unconnected-(U3-PC4(ADC4{slash}SDA)-Pad27)") (class "Default")
      (node (ref "U3") (pin "27") (pinfunction "PC4(ADC4/SDA)_27") (pintype "bidirectional"))
    )
    (net (code "77") (name "unconnected-(U3-PC5(ADC5{slash}SCL)-Pad28)") (class "Default")
      (node (ref "U3") (pin "28") (pinfunction "PC5(ADC5/SCL)_28") (pintype "bidirectional"))
    )
    (net (code "78") (name "unconnected-(U5-R232-Pad15)") (class "Default")
      (node (ref "U5") (pin "15") (pinfunction "R232_15") (pintype "bidirectional"))
    )
    (net (code "79") (name "unconnected-(U5-~{CTS}-Pad9)") (class "Default")
      (node (ref "U5") (pin "9") (pinfunction "~{CTS}_9") (pintype "bidirectional"))
    )
    (net (code "80") (name "unconnected-(U5-~{DCD}-Pad12)") (class "Default")
      (node (ref "U5") (pin "12") (pinfunction "~{DCD}_12") (pintype "bidirectional"))
    )
    (net (code "81") (name "unconnected-(U5-~{DSR}-Pad10)") (class "Default")
      (node (ref "U5") (pin "10") (pinfunction "~{DSR}_10") (pintype "bidirectional"))
    )
    (net (code "82") (name "unconnected-(U5-~{RI}-Pad11)") (class "Default")
      (node (ref "U5") (pin "11") (pinfunction "~{RI}_11") (pintype "bidirectional"))
    )
    (net (code "83") (name "unconnected-(U5-~{RTS}-Pad14)") (class "Default")
      (node (ref "U5") (pin "14") (pinfunction "~{RTS}_14") (pintype "bidirectional"))
    )
  )
)
